# 4.net
KiCad netlist of a schematic drawn in Altium Designer
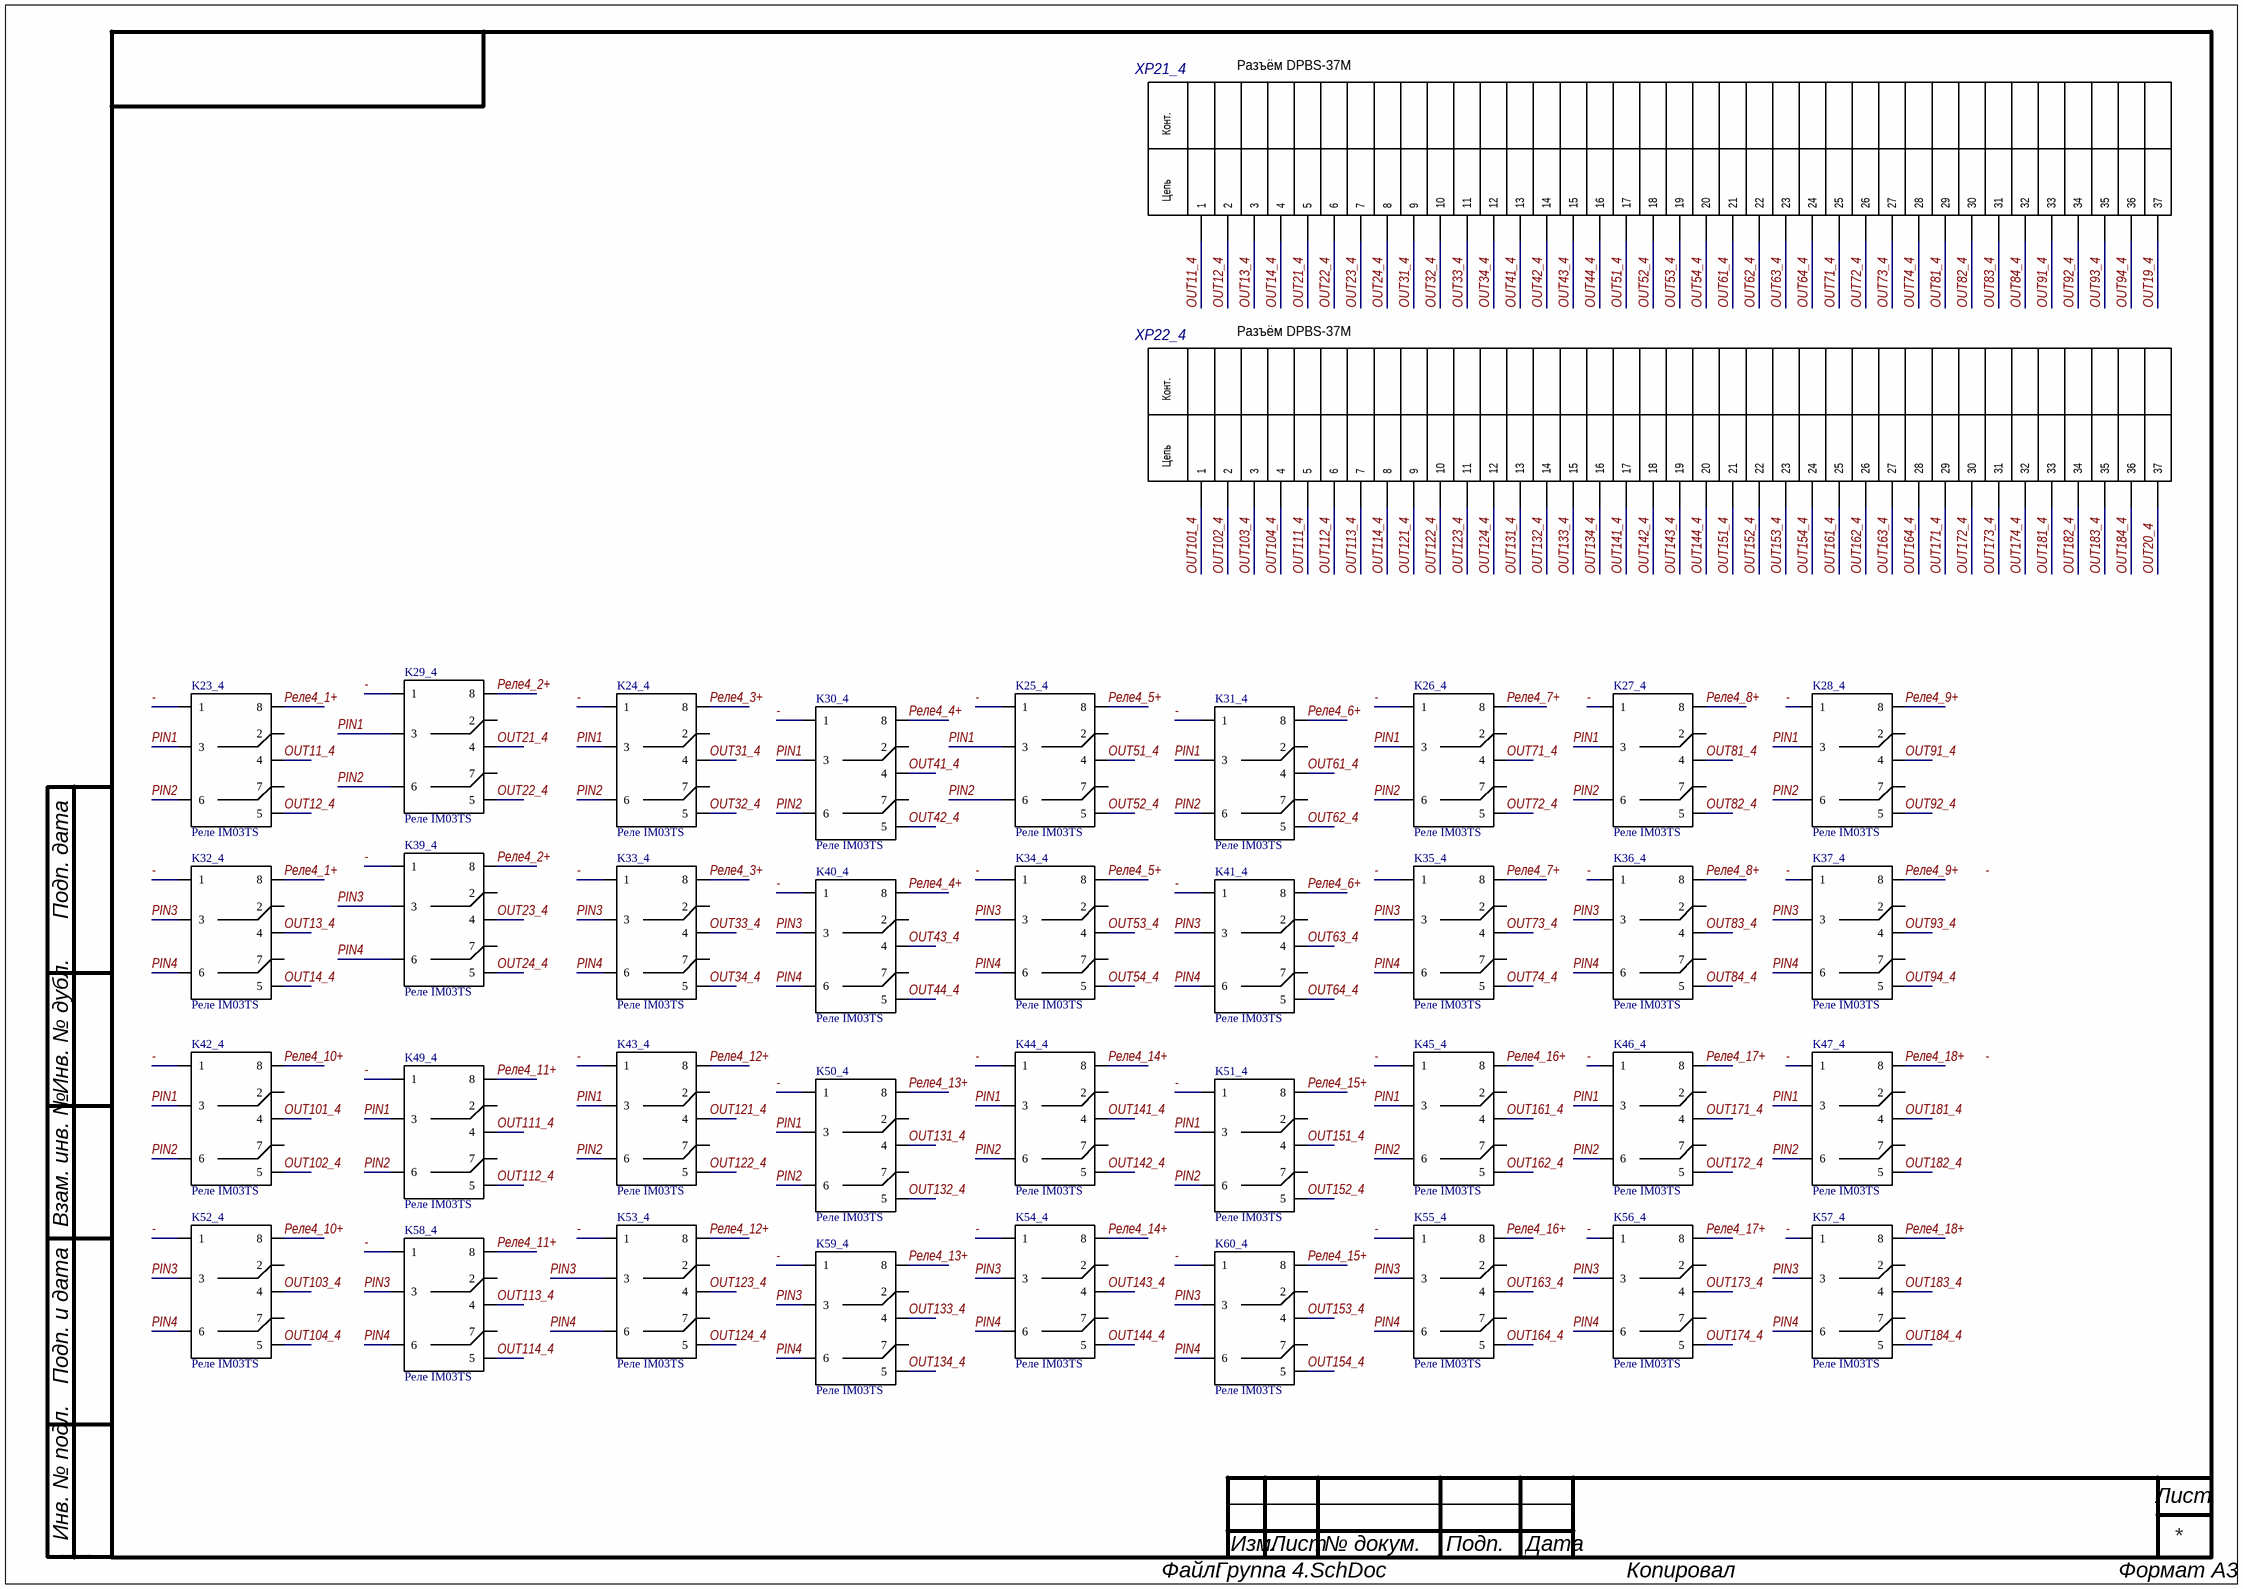
[diagram p0: Группа 4.SchDoc]

(export (version "E")
  (design (tool "Eeschema 10.0.6"))
  (components
    (comp (ref "K23_4")
      (value "Реле IM03TS")
      (footprint "IM03TS")
      (description "Реле")
      (libsource (lib "MainLibrary") (part "IM03TS"))
    )
    (comp (ref "K24_4")
      (value "Реле IM03TS")
      (footprint "IM03TS")
      (description "Реле")
      (libsource (lib "MainLibrary") (part "IM03TS"))
    )
    (comp (ref "K25_4")
      (value "Реле IM03TS")
      (footprint "IM03TS")
      (description "Реле")
      (libsource (lib "MainLibrary") (part "IM03TS"))
    )
    (comp (ref "K26_4")
      (value "Реле IM03TS")
      (footprint "IM03TS")
      (description "Реле")
      (libsource (lib "MainLibrary") (part "IM03TS"))
    )
    (comp (ref "K27_4")
      (value "Реле IM03TS")
      (footprint "IM03TS")
      (description "Реле")
      (libsource (lib "MainLibrary") (part "IM03TS"))
    )
    (comp (ref "K28_4")
      (value "Реле IM03TS")
      (footprint "IM03TS")
      (description "Реле")
      (libsource (lib "MainLibrary") (part "IM03TS"))
    )
    (comp (ref "K29_4")
      (value "Реле IM03TS")
      (footprint "IM03TS")
      (description "Реле")
      (libsource (lib "MainLibrary") (part "IM03TS"))
    )
    (comp (ref "K30_4")
      (value "Реле IM03TS")
      (footprint "IM03TS")
      (description "Реле")
      (libsource (lib "MainLibrary") (part "IM03TS"))
    )
    (comp (ref "K31_4")
      (value "Реле IM03TS")
      (footprint "IM03TS")
      (description "Реле")
      (libsource (lib "MainLibrary") (part "IM03TS"))
    )
    (comp (ref "K32_4")
      (value "Реле IM03TS")
      (footprint "IM03TS")
      (description "Реле")
      (libsource (lib "MainLibrary") (part "IM03TS"))
    )
    (comp (ref "K33_4")
      (value "Реле IM03TS")
      (footprint "IM03TS")
      (description "Реле")
      (libsource (lib "MainLibrary") (part "IM03TS"))
    )
    (comp (ref "K34_4")
      (value "Реле IM03TS")
      (footprint "IM03TS")
      (description "Реле")
      (libsource (lib "MainLibrary") (part "IM03TS"))
    )
    (comp (ref "K35_4")
      (value "Реле IM03TS")
      (footprint "IM03TS")
      (description "Реле")
      (libsource (lib "MainLibrary") (part "IM03TS"))
    )
    (comp (ref "K36_4")
      (value "Реле IM03TS")
      (footprint "IM03TS")
      (description "Реле")
      (libsource (lib "MainLibrary") (part "IM03TS"))
    )
    (comp (ref "K37_4")
      (value "Реле IM03TS")
      (footprint "IM03TS")
      (description "Реле")
      (libsource (lib "MainLibrary") (part "IM03TS"))
    )
    (comp (ref "K39_4")
      (value "Реле IM03TS")
      (footprint "IM03TS")
      (description "Реле")
      (libsource (lib "MainLibrary") (part "IM03TS"))
    )
    (comp (ref "K40_4")
      (value "Реле IM03TS")
      (footprint "IM03TS")
      (description "Реле")
      (libsource (lib "MainLibrary") (part "IM03TS"))
    )
    (comp (ref "K41_4")
      (value "Реле IM03TS")
      (footprint "IM03TS")
      (description "Реле")
      (libsource (lib "MainLibrary") (part "IM03TS"))
    )
    (comp (ref "K42_4")
      (value "Реле IM03TS")
      (footprint "IM03TS")
      (description "Реле")
      (libsource (lib "MainLibrary") (part "IM03TS"))
    )
    (comp (ref "K43_4")
      (value "Реле IM03TS")
      (footprint "IM03TS")
      (description "Реле")
      (libsource (lib "MainLibrary") (part "IM03TS"))
    )
    (comp (ref "K44_4")
      (value "Реле IM03TS")
      (footprint "IM03TS")
      (description "Реле")
      (libsource (lib "MainLibrary") (part "IM03TS"))
    )
    (comp (ref "K45_4")
      (value "Реле IM03TS")
      (footprint "IM03TS")
      (description "Реле")
      (libsource (lib "MainLibrary") (part "IM03TS"))
    )
    (comp (ref "K46_4")
      (value "Реле IM03TS")
      (footprint "IM03TS")
      (description "Реле")
      (libsource (lib "MainLibrary") (part "IM03TS"))
    )
    (comp (ref "K47_4")
      (value "Реле IM03TS")
      (footprint "IM03TS")
      (description "Реле")
      (libsource (lib "MainLibrary") (part "IM03TS"))
    )
    (comp (ref "K49_4")
      (value "Реле IM03TS")
      (footprint "IM03TS")
      (description "Реле")
      (libsource (lib "MainLibrary") (part "IM03TS"))
    )
    (comp (ref "K50_4")
      (value "Реле IM03TS")
      (footprint "IM03TS")
      (description "Реле")
      (libsource (lib "MainLibrary") (part "IM03TS"))
    )
    (comp (ref "K51_4")
      (value "Реле IM03TS")
      (footprint "IM03TS")
      (description "Реле")
      (libsource (lib "MainLibrary") (part "IM03TS"))
    )
    (comp (ref "K52_4")
      (value "Реле IM03TS")
      (footprint "IM03TS")
      (description "Реле")
      (libsource (lib "MainLibrary") (part "IM03TS"))
    )
    (comp (ref "K53_4")
      (value "Реле IM03TS")
      (footprint "IM03TS")
      (description "Реле")
      (libsource (lib "MainLibrary") (part "IM03TS"))
    )
    (comp (ref "K54_4")
      (value "Реле IM03TS")
      (footprint "IM03TS")
      (description "Реле")
      (libsource (lib "MainLibrary") (part "IM03TS"))
    )
    (comp (ref "K55_4")
      (value "Реле IM03TS")
      (footprint "IM03TS")
      (description "Реле")
      (libsource (lib "MainLibrary") (part "IM03TS"))
    )
    (comp (ref "K56_4")
      (value "Реле IM03TS")
      (footprint "IM03TS")
      (description "Реле")
      (libsource (lib "MainLibrary") (part "IM03TS"))
    )
    (comp (ref "K57_4")
      (value "Реле IM03TS")
      (footprint "IM03TS")
      (description "Реле")
      (libsource (lib "MainLibrary") (part "IM03TS"))
    )
    (comp (ref "K58_4")
      (value "Реле IM03TS")
      (footprint "IM03TS")
      (description "Реле")
      (libsource (lib "MainLibrary") (part "IM03TS"))
    )
    (comp (ref "K59_4")
      (value "Реле IM03TS")
      (footprint "IM03TS")
      (description "Реле")
      (libsource (lib "MainLibrary") (part "IM03TS"))
    )
    (comp (ref "K60_4")
      (value "Реле IM03TS")
      (footprint "IM03TS")
      (description "Реле")
      (libsource (lib "MainLibrary") (part "IM03TS"))
    )
    (comp (ref "XP21_4")
      (value "Разъём DPBS-37M")
      (footprint "DPBS-37M")
      (libsource (lib "MainLibrary") (part "DPBS-37M"))
    )
    (comp (ref "XP22_4")
      (value "Разъём DPBS-37M")
      (footprint "DPBS-37M")
      (libsource (lib "MainLibrary") (part "DPBS-37M"))
    )
  )
  (nets
    (net (code "1") (name "/-") (class "Default")
      (node (ref "K23_4") (pin "1") (pinfunction "1_1") (pintype "passive"))
      (node (ref "K24_4") (pin "1") (pinfunction "1_1") (pintype "passive"))
      (node (ref "K25_4") (pin "1") (pinfunction "1_1") (pintype "passive"))
      (node (ref "K26_4") (pin "1") (pinfunction "1_1") (pintype "passive"))
      (node (ref "K27_4") (pin "1") (pinfunction "1_1") (pintype "passive"))
      (node (ref "K28_4") (pin "1") (pinfunction "1_1") (pintype "passive"))
      (node (ref "K29_4") (pin "1") (pinfunction "1_1") (pintype "passive"))
      (node (ref "K30_4") (pin "1") (pinfunction "1_1") (pintype "passive"))
      (node (ref "K31_4") (pin "1") (pinfunction "1_1") (pintype "passive"))
      (node (ref "K32_4") (pin "1") (pinfunction "1_1") (pintype "passive"))
      (node (ref "K33_4") (pin "1") (pinfunction "1_1") (pintype "passive"))
      (node (ref "K34_4") (pin "1") (pinfunction "1_1") (pintype "passive"))
      (node (ref "K35_4") (pin "1") (pinfunction "1_1") (pintype "passive"))
      (node (ref "K36_4") (pin "1") (pinfunction "1_1") (pintype "passive"))
      (node (ref "K37_4") (pin "1") (pinfunction "1_1") (pintype "passive"))
      (node (ref "K39_4") (pin "1") (pinfunction "1_1") (pintype "passive"))
      (node (ref "K40_4") (pin "1") (pinfunction "1_1") (pintype "passive"))
      (node (ref "K41_4") (pin "1") (pinfunction "1_1") (pintype "passive"))
      (node (ref "K42_4") (pin "1") (pinfunction "1_1") (pintype "passive"))
      (node (ref "K43_4") (pin "1") (pinfunction "1_1") (pintype "passive"))
      (node (ref "K44_4") (pin "1") (pinfunction "1_1") (pintype "passive"))
      (node (ref "K45_4") (pin "1") (pinfunction "1_1") (pintype "passive"))
      (node (ref "K46_4") (pin "1") (pinfunction "1_1") (pintype "passive"))
      (node (ref "K47_4") (pin "1") (pinfunction "1_1") (pintype "passive"))
      (node (ref "K49_4") (pin "1") (pinfunction "1_1") (pintype "passive"))
      (node (ref "K50_4") (pin "1") (pinfunction "1_1") (pintype "passive"))
      (node (ref "K51_4") (pin "1") (pinfunction "1_1") (pintype "passive"))
      (node (ref "K52_4") (pin "1") (pinfunction "1_1") (pintype "passive"))
      (node (ref "K53_4") (pin "1") (pinfunction "1_1") (pintype "passive"))
      (node (ref "K54_4") (pin "1") (pinfunction "1_1") (pintype "passive"))
      (node (ref "K55_4") (pin "1") (pinfunction "1_1") (pintype "passive"))
      (node (ref "K56_4") (pin "1") (pinfunction "1_1") (pintype "passive"))
      (node (ref "K57_4") (pin "1") (pinfunction "1_1") (pintype "passive"))
      (node (ref "K58_4") (pin "1") (pinfunction "1_1") (pintype "passive"))
      (node (ref "K59_4") (pin "1") (pinfunction "1_1") (pintype "passive"))
      (node (ref "K60_4") (pin "1") (pinfunction "1_1") (pintype "passive"))
    )
    (net (code "2") (name "/OUT11_4") (class "Default")
      (node (ref "K23_4") (pin "4") (pinfunction "4_4") (pintype "passive"))
      (node (ref "XP21_4") (pin "1") (pinfunction "1_1") (pintype "passive"))
    )
    (net (code "3") (name "/OUT12_4") (class "Default")
      (node (ref "K23_4") (pin "5") (pinfunction "5_5") (pintype "passive"))
      (node (ref "XP21_4") (pin "2") (pinfunction "2_2") (pintype "passive"))
    )
    (net (code "4") (name "/OUT13_4") (class "Default")
      (node (ref "K32_4") (pin "4") (pinfunction "4_4") (pintype "passive"))
      (node (ref "XP21_4") (pin "3") (pinfunction "3_3") (pintype "passive"))
    )
    (net (code "5") (name "/OUT14_4") (class "Default")
      (node (ref "K32_4") (pin "5") (pinfunction "5_5") (pintype "passive"))
      (node (ref "XP21_4") (pin "4") (pinfunction "4_4") (pintype "passive"))
    )
    (net (code "6") (name "/OUT19_4") (class "Default")
      (node (ref "XP21_4") (pin "37") (pinfunction "37_37") (pintype "passive"))
    )
    (net (code "7") (name "/OUT20_4") (class "Default")
      (node (ref "XP22_4") (pin "37") (pinfunction "37_37") (pintype "passive"))
    )
    (net (code "8") (name "/OUT21_4") (class "Default")
      (node (ref "K29_4") (pin "4") (pinfunction "4_4") (pintype "passive"))
      (node (ref "XP21_4") (pin "5") (pinfunction "5_5") (pintype "passive"))
    )
    (net (code "9") (name "/OUT22_4") (class "Default")
      (node (ref "K29_4") (pin "5") (pinfunction "5_5") (pintype "passive"))
      (node (ref "XP21_4") (pin "6") (pinfunction "6_6") (pintype "passive"))
    )
    (net (code "10") (name "/OUT23_4") (class "Default")
      (node (ref "K39_4") (pin "4") (pinfunction "4_4") (pintype "passive"))
      (node (ref "XP21_4") (pin "7") (pinfunction "7_7") (pintype "passive"))
    )
    (net (code "11") (name "/OUT24_4") (class "Default")
      (node (ref "K39_4") (pin "5") (pinfunction "5_5") (pintype "passive"))
      (node (ref "XP21_4") (pin "8") (pinfunction "8_8") (pintype "passive"))
    )
    (net (code "12") (name "/OUT31_4") (class "Default")
      (node (ref "K24_4") (pin "4") (pinfunction "4_4") (pintype "passive"))
      (node (ref "XP21_4") (pin "9") (pinfunction "9_9") (pintype "passive"))
    )
    (net (code "13") (name "/OUT32_4") (class "Default")
      (node (ref "K24_4") (pin "5") (pinfunction "5_5") (pintype "passive"))
      (node (ref "XP21_4") (pin "10") (pinfunction "10_10") (pintype "passive"))
    )
    (net (code "14") (name "/OUT33_4") (class "Default")
      (node (ref "K33_4") (pin "4") (pinfunction "4_4") (pintype "passive"))
      (node (ref "XP21_4") (pin "11") (pinfunction "11_11") (pintype "passive"))
    )
    (net (code "15") (name "/OUT34_4") (class "Default")
      (node (ref "K33_4") (pin "5") (pinfunction "5_5") (pintype "passive"))
      (node (ref "XP21_4") (pin "12") (pinfunction "12_12") (pintype "passive"))
    )
    (net (code "16") (name "/OUT41_4") (class "Default")
      (node (ref "K30_4") (pin "4") (pinfunction "4_4") (pintype "passive"))
      (node (ref "XP21_4") (pin "13") (pinfunction "13_13") (pintype "passive"))
    )
    (net (code "17") (name "/OUT42_4") (class "Default")
      (node (ref "K30_4") (pin "5") (pinfunction "5_5") (pintype "passive"))
      (node (ref "XP21_4") (pin "14") (pinfunction "14_14") (pintype "passive"))
    )
    (net (code "18") (name "/OUT43_4") (class "Default")
      (node (ref "K40_4") (pin "4") (pinfunction "4_4") (pintype "passive"))
      (node (ref "XP21_4") (pin "15") (pinfunction "15_15") (pintype "passive"))
    )
    (net (code "19") (name "/OUT44_4") (class "Default")
      (node (ref "K40_4") (pin "5") (pinfunction "5_5") (pintype "passive"))
      (node (ref "XP21_4") (pin "16") (pinfunction "16_16") (pintype "passive"))
    )
    (net (code "20") (name "/OUT51_4") (class "Default")
      (node (ref "K25_4") (pin "4") (pinfunction "4_4") (pintype "passive"))
      (node (ref "XP21_4") (pin "17") (pinfunction "17_17") (pintype "passive"))
    )
    (net (code "21") (name "/OUT52_4") (class "Default")
      (node (ref "K25_4") (pin "5") (pinfunction "5_5") (pintype "passive"))
      (node (ref "XP21_4") (pin "18") (pinfunction "18_18") (pintype "passive"))
    )
    (net (code "22") (name "/OUT53_4") (class "Default")
      (node (ref "K34_4") (pin "4") (pinfunction "4_4") (pintype "passive"))
      (node (ref "XP21_4") (pin "19") (pinfunction "19_19") (pintype "passive"))
    )
    (net (code "23") (name "/OUT54_4") (class "Default")
      (node (ref "K34_4") (pin "5") (pinfunction "5_5") (pintype "passive"))
      (node (ref "XP21_4") (pin "20") (pinfunction "20_20") (pintype "passive"))
    )
    (net (code "24") (name "/OUT61_4") (class "Default")
      (node (ref "K31_4") (pin "4") (pinfunction "4_4") (pintype "passive"))
      (node (ref "XP21_4") (pin "21") (pinfunction "21_21") (pintype "passive"))
    )
    (net (code "25") (name "/OUT62_4") (class "Default")
      (node (ref "K31_4") (pin "5") (pinfunction "5_5") (pintype "passive"))
      (node (ref "XP21_4") (pin "22") (pinfunction "22_22") (pintype "passive"))
    )
    (net (code "26") (name "/OUT63_4") (class "Default")
      (node (ref "K41_4") (pin "4") (pinfunction "4_4") (pintype "passive"))
      (node (ref "XP21_4") (pin "23") (pinfunction "23_23") (pintype "passive"))
    )
    (net (code "27") (name "/OUT64_4") (class "Default")
      (node (ref "K41_4") (pin "5") (pinfunction "5_5") (pintype "passive"))
      (node (ref "XP21_4") (pin "24") (pinfunction "24_24") (pintype "passive"))
    )
    (net (code "28") (name "/OUT71_4") (class "Default")
      (node (ref "K26_4") (pin "4") (pinfunction "4_4") (pintype "passive"))
      (node (ref "XP21_4") (pin "25") (pinfunction "25_25") (pintype "passive"))
    )
    (net (code "29") (name "/OUT72_4") (class "Default")
      (node (ref "K26_4") (pin "5") (pinfunction "5_5") (pintype "passive"))
      (node (ref "XP21_4") (pin "26") (pinfunction "26_26") (pintype "passive"))
    )
    (net (code "30") (name "/OUT73_4") (class "Default")
      (node (ref "K35_4") (pin "4") (pinfunction "4_4") (pintype "passive"))
      (node (ref "XP21_4") (pin "27") (pinfunction "27_27") (pintype "passive"))
    )
    (net (code "31") (name "/OUT74_4") (class "Default")
      (node (ref "K35_4") (pin "5") (pinfunction "5_5") (pintype "passive"))
      (node (ref "XP21_4") (pin "28") (pinfunction "28_28") (pintype "passive"))
    )
    (net (code "32") (name "/OUT81_4") (class "Default")
      (node (ref "K27_4") (pin "4") (pinfunction "4_4") (pintype "passive"))
      (node (ref "XP21_4") (pin "29") (pinfunction "29_29") (pintype "passive"))
    )
    (net (code "33") (name "/OUT82_4") (class "Default")
      (node (ref "K27_4") (pin "5") (pinfunction "5_5") (pintype "passive"))
      (node (ref "XP21_4") (pin "30") (pinfunction "30_30") (pintype "passive"))
    )
    (net (code "34") (name "/OUT83_4") (class "Default")
      (node (ref "K36_4") (pin "4") (pinfunction "4_4") (pintype "passive"))
      (node (ref "XP21_4") (pin "31") (pinfunction "31_31") (pintype "passive"))
    )
    (net (code "35") (name "/OUT84_4") (class "Default")
      (node (ref "K36_4") (pin "5") (pinfunction "5_5") (pintype "passive"))
      (node (ref "XP21_4") (pin "32") (pinfunction "32_32") (pintype "passive"))
    )
    (net (code "36") (name "/OUT91_4") (class "Default")
      (node (ref "K28_4") (pin "4") (pinfunction "4_4") (pintype "passive"))
      (node (ref "XP21_4") (pin "33") (pinfunction "33_33") (pintype "passive"))
    )
    (net (code "37") (name "/OUT92_4") (class "Default")
      (node (ref "K28_4") (pin "5") (pinfunction "5_5") (pintype "passive"))
      (node (ref "XP21_4") (pin "34") (pinfunction "34_34") (pintype "passive"))
    )
    (net (code "38") (name "/OUT93_4") (class "Default")
      (node (ref "K37_4") (pin "4") (pinfunction "4_4") (pintype "passive"))
      (node (ref "XP21_4") (pin "35") (pinfunction "35_35") (pintype "passive"))
    )
    (net (code "39") (name "/OUT94_4") (class "Default")
      (node (ref "K37_4") (pin "5") (pinfunction "5_5") (pintype "passive"))
      (node (ref "XP21_4") (pin "36") (pinfunction "36_36") (pintype "passive"))
    )
    (net (code "40") (name "/OUT101_4") (class "Default")
      (node (ref "K42_4") (pin "4") (pinfunction "4_4") (pintype "passive"))
      (node (ref "XP22_4") (pin "1") (pinfunction "1_1") (pintype "passive"))
    )
    (net (code "41") (name "/OUT102_4") (class "Default")
      (node (ref "K42_4") (pin "5") (pinfunction "5_5") (pintype "passive"))
      (node (ref "XP22_4") (pin "2") (pinfunction "2_2") (pintype "passive"))
    )
    (net (code "42") (name "/OUT103_4") (class "Default")
      (node (ref "K52_4") (pin "4") (pinfunction "4_4") (pintype "passive"))
      (node (ref "XP22_4") (pin "3") (pinfunction "3_3") (pintype "passive"))
    )
    (net (code "43") (name "/OUT104_4") (class "Default")
      (node (ref "K52_4") (pin "5") (pinfunction "5_5") (pintype "passive"))
      (node (ref "XP22_4") (pin "4") (pinfunction "4_4") (pintype "passive"))
    )
    (net (code "44") (name "/OUT111_4") (class "Default")
      (node (ref "K49_4") (pin "4") (pinfunction "4_4") (pintype "passive"))
      (node (ref "XP22_4") (pin "5") (pinfunction "5_5") (pintype "passive"))
    )
    (net (code "45") (name "/OUT112_4") (class "Default")
      (node (ref "K49_4") (pin "5") (pinfunction "5_5") (pintype "passive"))
      (node (ref "XP22_4") (pin "6") (pinfunction "6_6") (pintype "passive"))
    )
    (net (code "46") (name "/OUT113_4") (class "Default")
      (node (ref "K58_4") (pin "4") (pinfunction "4_4") (pintype "passive"))
      (node (ref "XP22_4") (pin "7") (pinfunction "7_7") (pintype "passive"))
    )
    (net (code "47") (name "/OUT114_4") (class "Default")
      (node (ref "K58_4") (pin "5") (pinfunction "5_5") (pintype "passive"))
      (node (ref "XP22_4") (pin "8") (pinfunction "8_8") (pintype "passive"))
    )
    (net (code "48") (name "/OUT121_4") (class "Default")
      (node (ref "K43_4") (pin "4") (pinfunction "4_4") (pintype "passive"))
      (node (ref "XP22_4") (pin "9") (pinfunction "9_9") (pintype "passive"))
    )
    (net (code "49") (name "/OUT122_4") (class "Default")
      (node (ref "K43_4") (pin "5") (pinfunction "5_5") (pintype "passive"))
      (node (ref "XP22_4") (pin "10") (pinfunction "10_10") (pintype "passive"))
    )
    (net (code "50") (name "/OUT123_4") (class "Default")
      (node (ref "K53_4") (pin "4") (pinfunction "4_4") (pintype "passive"))
      (node (ref "XP22_4") (pin "11") (pinfunction "11_11") (pintype "passive"))
    )
    (net (code "51") (name "/OUT124_4") (class "Default")
      (node (ref "K53_4") (pin "5") (pinfunction "5_5") (pintype "passive"))
      (node (ref "XP22_4") (pin "12") (pinfunction "12_12") (pintype "passive"))
    )
    (net (code "52") (name "/OUT131_4") (class "Default")
      (node (ref "K50_4") (pin "4") (pinfunction "4_4") (pintype "passive"))
      (node (ref "XP22_4") (pin "13") (pinfunction "13_13") (pintype "passive"))
    )
    (net (code "53") (name "/OUT132_4") (class "Default")
      (node (ref "K50_4") (pin "5") (pinfunction "5_5") (pintype "passive"))
      (node (ref "XP22_4") (pin "14") (pinfunction "14_14") (pintype "passive"))
    )
    (net (code "54") (name "/OUT133_4") (class "Default")
      (node (ref "K59_4") (pin "4") (pinfunction "4_4") (pintype "passive"))
      (node (ref "XP22_4") (pin "15") (pinfunction "15_15") (pintype "passive"))
    )
    (net (code "55") (name "/OUT134_4") (class "Default")
      (node (ref "K59_4") (pin "5") (pinfunction "5_5") (pintype "passive"))
      (node (ref "XP22_4") (pin "16") (pinfunction "16_16") (pintype "passive"))
    )
    (net (code "56") (name "/OUT141_4") (class "Default")
      (node (ref "K44_4") (pin "4") (pinfunction "4_4") (pintype "passive"))
      (node (ref "XP22_4") (pin "17") (pinfunction "17_17") (pintype "passive"))
    )
    (net (code "57") (name "/OUT142_4") (class "Default")
      (node (ref "K44_4") (pin "5") (pinfunction "5_5") (pintype "passive"))
      (node (ref "XP22_4") (pin "18") (pinfunction "18_18") (pintype "passive"))
    )
    (net (code "58") (name "/OUT143_4") (class "Default")
      (node (ref "K54_4") (pin "4") (pinfunction "4_4") (pintype "passive"))
      (node (ref "XP22_4") (pin "19") (pinfunction "19_19") (pintype "passive"))
    )
    (net (code "59") (name "/OUT144_4") (class "Default")
      (node (ref "K54_4") (pin "5") (pinfunction "5_5") (pintype "passive"))
      (node (ref "XP22_4") (pin "20") (pinfunction "20_20") (pintype "passive"))
    )
    (net (code "60") (name "/OUT151_4") (class "Default")
      (node (ref "K51_4") (pin "4") (pinfunction "4_4") (pintype "passive"))
      (node (ref "XP22_4") (pin "21") (pinfunction "21_21") (pintype "passive"))
    )
    (net (code "61") (name "/OUT152_4") (class "Default")
      (node (ref "K51_4") (pin "5") (pinfunction "5_5") (pintype "passive"))
      (node (ref "XP22_4") (pin "22") (pinfunction "22_22") (pintype "passive"))
    )
    (net (code "62") (name "/OUT153_4") (class "Default")
      (node (ref "K60_4") (pin "4") (pinfunction "4_4") (pintype "passive"))
      (node (ref "XP22_4") (pin "23") (pinfunction "23_23") (pintype "passive"))
    )
    (net (code "63") (name "/OUT154_4") (class "Default")
      (node (ref "K60_4") (pin "5") (pinfunction "5_5") (pintype "passive"))
      (node (ref "XP22_4") (pin "24") (pinfunction "24_24") (pintype "passive"))
    )
    (net (code "64") (name "/OUT161_4") (class "Default")
      (node (ref "K45_4") (pin "4") (pinfunction "4_4") (pintype "passive"))
      (node (ref "XP22_4") (pin "25") (pinfunction "25_25") (pintype "passive"))
    )
    (net (code "65") (name "/OUT162_4") (class "Default")
      (node (ref "K45_4") (pin "5") (pinfunction "5_5") (pintype "passive"))
      (node (ref "XP22_4") (pin "26") (pinfunction "26_26") (pintype "passive"))
    )
    (net (code "66") (name "/OUT163_4") (class "Default")
      (node (ref "K55_4") (pin "4") (pinfunction "4_4") (pintype "passive"))
      (node (ref "XP22_4") (pin "27") (pinfunction "27_27") (pintype "passive"))
    )
    (net (code "67") (name "/OUT164_4") (class "Default")
      (node (ref "K55_4") (pin "5") (pinfunction "5_5") (pintype "passive"))
      (node (ref "XP22_4") (pin "28") (pinfunction "28_28") (pintype "passive"))
    )
    (net (code "68") (name "/OUT171_4") (class "Default")
      (node (ref "K46_4") (pin "4") (pinfunction "4_4") (pintype "passive"))
      (node (ref "XP22_4") (pin "29") (pinfunction "29_29") (pintype "passive"))
    )
    (net (code "69") (name "/OUT172_4") (class "Default")
      (node (ref "K46_4") (pin "5") (pinfunction "5_5") (pintype "passive"))
      (node (ref "XP22_4") (pin "30") (pinfunction "30_30") (pintype "passive"))
    )
    (net (code "70") (name "/OUT173_4") (class "Default")
      (node (ref "K56_4") (pin "4") (pinfunction "4_4") (pintype "passive"))
      (node (ref "XP22_4") (pin "31") (pinfunction "31_31") (pintype "passive"))
    )
    (net (code "71") (name "/OUT174_4") (class "Default")
      (node (ref "K56_4") (pin "5") (pinfunction "5_5") (pintype "passive"))
      (node (ref "XP22_4") (pin "32") (pinfunction "32_32") (pintype "passive"))
    )
    (net (code "72") (name "/OUT181_4") (class "Default")
      (node (ref "K47_4") (pin "4") (pinfunction "4_4") (pintype "passive"))
      (node (ref "XP22_4") (pin "33") (pinfunction "33_33") (pintype "passive"))
    )
    (net (code "73") (name "/OUT182_4") (class "Default")
      (node (ref "K47_4") (pin "5") (pinfunction "5_5") (pintype "passive"))
      (node (ref "XP22_4") (pin "34") (pinfunction "34_34") (pintype "passive"))
    )
    (net (code "74") (name "/OUT183_4") (class "Default")
      (node (ref "K57_4") (pin "4") (pinfunction "4_4") (pintype "passive"))
      (node (ref "XP22_4") (pin "35") (pinfunction "35_35") (pintype "passive"))
    )
    (net (code "75") (name "/OUT184_4") (class "Default")
      (node (ref "K57_4") (pin "5") (pinfunction "5_5") (pintype "passive"))
      (node (ref "XP22_4") (pin "36") (pinfunction "36_36") (pintype "passive"))
    )
    (net (code "76") (name "/PIN1") (class "Default")
      (node (ref "K23_4") (pin "3") (pinfunction "3_3") (pintype "passive"))
      (node (ref "K24_4") (pin "3") (pinfunction "3_3") (pintype "passive"))
      (node (ref "K25_4") (pin "3") (pinfunction "3_3") (pintype "passive"))
      (node (ref "K26_4") (pin "3") (pinfunction "3_3") (pintype "passive"))
      (node (ref "K27_4") (pin "3") (pinfunction "3_3") (pintype "passive"))
      (node (ref "K28_4") (pin "3") (pinfunction "3_3") (pintype "passive"))
      (node (ref "K29_4") (pin "3") (pinfunction "3_3") (pintype "passive"))
      (node (ref "K30_4") (pin "3") (pinfunction "3_3") (pintype "passive"))
      (node (ref "K31_4") (pin "3") (pinfunction "3_3") (pintype "passive"))
      (node (ref "K42_4") (pin "3") (pinfunction "3_3") (pintype "passive"))
      (node (ref "K43_4") (pin "3") (pinfunction "3_3") (pintype "passive"))
      (node (ref "K44_4") (pin "3") (pinfunction "3_3") (pintype "passive"))
      (node (ref "K45_4") (pin "3") (pinfunction "3_3") (pintype "passive"))
      (node (ref "K46_4") (pin "3") (pinfunction "3_3") (pintype "passive"))
      (node (ref "K47_4") (pin "3") (pinfunction "3_3") (pintype "passive"))
      (node (ref "K49_4") (pin "3") (pinfunction "3_3") (pintype "passive"))
      (node (ref "K50_4") (pin "3") (pinfunction "3_3") (pintype "passive"))
      (node (ref "K51_4") (pin "3") (pinfunction "3_3") (pintype "passive"))
    )
    (net (code "77") (name "/PIN2") (class "Default")
      (node (ref "K23_4") (pin "6") (pinfunction "6_6") (pintype "passive"))
      (node (ref "K24_4") (pin "6") (pinfunction "6_6") (pintype "passive"))
      (node (ref "K25_4") (pin "6") (pinfunction "6_6") (pintype "passive"))
      (node (ref "K26_4") (pin "6") (pinfunction "6_6") (pintype "passive"))
      (node (ref "K27_4") (pin "6") (pinfunction "6_6") (pintype "passive"))
      (node (ref "K28_4") (pin "6") (pinfunction "6_6") (pintype "passive"))
      (node (ref "K29_4") (pin "6") (pinfunction "6_6") (pintype "passive"))
      (node (ref "K30_4") (pin "6") (pinfunction "6_6") (pintype "passive"))
      (node (ref "K31_4") (pin "6") (pinfunction "6_6") (pintype "passive"))
      (node (ref "K42_4") (pin "6") (pinfunction "6_6") (pintype "passive"))
      (node (ref "K43_4") (pin "6") (pinfunction "6_6") (pintype "passive"))
      (node (ref "K44_4") (pin "6") (pinfunction "6_6") (pintype "passive"))
      (node (ref "K45_4") (pin "6") (pinfunction "6_6") (pintype "passive"))
      (node (ref "K46_4") (pin "6") (pinfunction "6_6") (pintype "passive"))
      (node (ref "K47_4") (pin "6") (pinfunction "6_6") (pintype "passive"))
      (node (ref "K49_4") (pin "6") (pinfunction "6_6") (pintype "passive"))
      (node (ref "K50_4") (pin "6") (pinfunction "6_6") (pintype "passive"))
      (node (ref "K51_4") (pin "6") (pinfunction "6_6") (pintype "passive"))
    )
    (net (code "78") (name "/PIN3") (class "Default")
      (node (ref "K32_4") (pin "3") (pinfunction "3_3") (pintype "passive"))
      (node (ref "K33_4") (pin "3") (pinfunction "3_3") (pintype "passive"))
      (node (ref "K34_4") (pin "3") (pinfunction "3_3") (pintype "passive"))
      (node (ref "K35_4") (pin "3") (pinfunction "3_3") (pintype "passive"))
      (node (ref "K36_4") (pin "3") (pinfunction "3_3") (pintype "passive"))
      (node (ref "K37_4") (pin "3") (pinfunction "3_3") (pintype "passive"))
      (node (ref "K39_4") (pin "3") (pinfunction "3_3") (pintype "passive"))
      (node (ref "K40_4") (pin "3") (pinfunction "3_3") (pintype "passive"))
      (node (ref "K41_4") (pin "3") (pinfunction "3_3") (pintype "passive"))
      (node (ref "K52_4") (pin "3") (pinfunction "3_3") (pintype "passive"))
      (node (ref "K53_4") (pin "3") (pinfunction "3_3") (pintype "passive"))
      (node (ref "K54_4") (pin "3") (pinfunction "3_3") (pintype "passive"))
      (node (ref "K55_4") (pin "3") (pinfunction "3_3") (pintype "passive"))
      (node (ref "K56_4") (pin "3") (pinfunction "3_3") (pintype "passive"))
      (node (ref "K57_4") (pin "3") (pinfunction "3_3") (pintype "passive"))
      (node (ref "K58_4") (pin "3") (pinfunction "3_3") (pintype "passive"))
      (node (ref "K59_4") (pin "3") (pinfunction "3_3") (pintype "passive"))
      (node (ref "K60_4") (pin "3") (pinfunction "3_3") (pintype "passive"))
    )
    (net (code "79") (name "/PIN4") (class "Default")
      (node (ref "K32_4") (pin "6") (pinfunction "6_6") (pintype "passive"))
      (node (ref "K33_4") (pin "6") (pinfunction "6_6") (pintype "passive"))
      (node (ref "K34_4") (pin "6") (pinfunction "6_6") (pintype "passive"))
      (node (ref "K35_4") (pin "6") (pinfunction "6_6") (pintype "passive"))
      (node (ref "K36_4") (pin "6") (pinfunction "6_6") (pintype "passive"))
      (node (ref "K37_4") (pin "6") (pinfunction "6_6") (pintype "passive"))
      (node (ref "K39_4") (pin "6") (pinfunction "6_6") (pintype "passive"))
      (node (ref "K40_4") (pin "6") (pinfunction "6_6") (pintype "passive"))
      (node (ref "K41_4") (pin "6") (pinfunction "6_6") (pintype "passive"))
      (node (ref "K52_4") (pin "6") (pinfunction "6_6") (pintype "passive"))
      (node (ref "K53_4") (pin "6") (pinfunction "6_6") (pintype "passive"))
      (node (ref "K54_4") (pin "6") (pinfunction "6_6") (pintype "passive"))
      (node (ref "K55_4") (pin "6") (pinfunction "6_6") (pintype "passive"))
      (node (ref "K56_4") (pin "6") (pinfunction "6_6") (pintype "passive"))
      (node (ref "K57_4") (pin "6") (pinfunction "6_6") (pintype "passive"))
      (node (ref "K58_4") (pin "6") (pinfunction "6_6") (pintype "passive"))
      (node (ref "K59_4") (pin "6") (pinfunction "6_6") (pintype "passive"))
      (node (ref "K60_4") (pin "6") (pinfunction "6_6") (pintype "passive"))
    )
    (net (code "80") (name "/Реле4_1+") (class "Default")
      (node (ref "K23_4") (pin "8") (pinfunction "8_8") (pintype "passive"))
      (node (ref "K32_4") (pin "8") (pinfunction "8_8") (pintype "passive"))
    )
    (net (code "81") (name "/Реле4_2+") (class "Default")
      (node (ref "K29_4") (pin "8") (pinfunction "8_8") (pintype "passive"))
      (node (ref "K39_4") (pin "8") (pinfunction "8_8") (pintype "passive"))
    )
    (net (code "82") (name "/Реле4_3+") (class "Default")
      (node (ref "K24_4") (pin "8") (pinfunction "8_8") (pintype "passive"))
      (node (ref "K33_4") (pin "8") (pinfunction "8_8") (pintype "passive"))
    )
    (net (code "83") (name "/Реле4_4+") (class "Default")
      (node (ref "K30_4") (pin "8") (pinfunction "8_8") (pintype "passive"))
      (node (ref "K40_4") (pin "8") (pinfunction "8_8") (pintype "passive"))
    )
    (net (code "84") (name "/Реле4_5+") (class "Default")
      (node (ref "K25_4") (pin "8") (pinfunction "8_8") (pintype "passive"))
      (node (ref "K34_4") (pin "8") (pinfunction "8_8") (pintype "passive"))
    )
    (net (code "85") (name "/Реле4_6+") (class "Default")
      (node (ref "K31_4") (pin "8") (pinfunction "8_8") (pintype "passive"))
      (node (ref "K41_4") (pin "8") (pinfunction "8_8") (pintype "passive"))
    )
    (net (code "86") (name "/Реле4_7+") (class "Default")
      (node (ref "K26_4") (pin "8") (pinfunction "8_8") (pintype "passive"))
      (node (ref "K35_4") (pin "8") (pinfunction "8_8") (pintype "passive"))
    )
    (net (code "87") (name "/Реле4_8+") (class "Default")
      (node (ref "K27_4") (pin "8") (pinfunction "8_8") (pintype "passive"))
      (node (ref "K36_4") (pin "8") (pinfunction "8_8") (pintype "passive"))
    )
    (net (code "88") (name "/Реле4_9+") (class "Default")
      (node (ref "K28_4") (pin "8") (pinfunction "8_8") (pintype "passive"))
      (node (ref "K37_4") (pin "8") (pinfunction "8_8") (pintype "passive"))
    )
    (net (code "89") (name "/Реле4_10+") (class "Default")
      (node (ref "K42_4") (pin "8") (pinfunction "8_8") (pintype "passive"))
      (node (ref "K52_4") (pin "8") (pinfunction "8_8") (pintype "passive"))
    )
    (net (code "90") (name "/Реле4_11+") (class "Default")
      (node (ref "K49_4") (pin "8") (pinfunction "8_8") (pintype "passive"))
      (node (ref "K58_4") (pin "8") (pinfunction "8_8") (pintype "passive"))
    )
    (net (code "91") (name "/Реле4_12+") (class "Default")
      (node (ref "K43_4") (pin "8") (pinfunction "8_8") (pintype "passive"))
      (node (ref "K53_4") (pin "8") (pinfunction "8_8") (pintype "passive"))
    )
    (net (code "92") (name "/Реле4_13+") (class "Default")
      (node (ref "K50_4") (pin "8") (pinfunction "8_8") (pintype "passive"))
      (node (ref "K59_4") (pin "8") (pinfunction "8_8") (pintype "passive"))
    )
    (net (code "93") (name "/Реле4_14+") (class "Default")
      (node (ref "K44_4") (pin "8") (pinfunction "8_8") (pintype "passive"))
      (node (ref "K54_4") (pin "8") (pinfunction "8_8") (pintype "passive"))
    )
    (net (code "94") (name "/Реле4_15+") (class "Default")
      (node (ref "K51_4") (pin "8") (pinfunction "8_8") (pintype "passive"))
      (node (ref "K60_4") (pin "8") (pinfunction "8_8") (pintype "passive"))
    )
    (net (code "95") (name "/Реле4_16+") (class "Default")
      (node (ref "K45_4") (pin "8") (pinfunction "8_8") (pintype "passive"))
      (node (ref "K55_4") (pin "8") (pinfunction "8_8") (pintype "passive"))
    )
    (net (code "96") (name "/Реле4_17+") (class "Default")
      (node (ref "K46_4") (pin "8") (pinfunction "8_8") (pintype "passive"))
      (node (ref "K56_4") (pin "8") (pinfunction "8_8") (pintype "passive"))
    )
    (net (code "97") (name "/Реле4_18+") (class "Default")
      (node (ref "K47_4") (pin "8") (pinfunction "8_8") (pintype "passive"))
      (node (ref "K57_4") (pin "8") (pinfunction "8_8") (pintype "passive"))
    )
    (net (code "98") (name "unconnected-(K23_4-Pad2)") (class "Default")
      (node (ref "K23_4") (pin "2") (pinfunction "2_2") (pintype "passive"))
    )
    (net (code "99") (name "unconnected-(K23_4-Pad7)") (class "Default")
      (node (ref "K23_4") (pin "7") (pinfunction "7_7") (pintype "passive"))
    )
    (net (code "100") (name "unconnected-(K24_4-Pad2)") (class "Default")
      (node (ref "K24_4") (pin "2") (pinfunction "2_2") (pintype "passive"))
    )
    (net (code "101") (name "unconnected-(K24_4-Pad7)") (class "Default")
      (node (ref "K24_4") (pin "7") (pinfunction "7_7") (pintype "passive"))
    )
    (net (code "102") (name "unconnected-(K25_4-Pad2)") (class "Default")
      (node (ref "K25_4") (pin "2") (pinfunction "2_2") (pintype "passive"))
    )
    (net (code "103") (name "unconnected-(K25_4-Pad7)") (class "Default")
      (node (ref "K25_4") (pin "7") (pinfunction "7_7") (pintype "passive"))
    )
    (net (code "104") (name "unconnected-(K26_4-Pad2)") (class "Default")
      (node (ref "K26_4") (pin "2") (pinfunction "2_2") (pintype "passive"))
    )
    (net (code "105") (name "unconnected-(K26_4-Pad7)") (class "Default")
      (node (ref "K26_4") (pin "7") (pinfunction "7_7") (pintype "passive"))
    )
    (net (code "106") (name "unconnected-(K27_4-Pad2)") (class "Default")
      (node (ref "K27_4") (pin "2") (pinfunction "2_2") (pintype "passive"))
    )
    (net (code "107") (name "unconnected-(K27_4-Pad7)") (class "Default")
      (node (ref "K27_4") (pin "7") (pinfunction "7_7") (pintype "passive"))
    )
    (net (code "108") (name "unconnected-(K28_4-Pad2)") (class "Default")
      (node (ref "K28_4") (pin "2") (pinfunction "2_2") (pintype "passive"))
    )
    (net (code "109") (name "unconnected-(K28_4-Pad7)") (class "Default")
      (node (ref "K28_4") (pin "7") (pinfunction "7_7") (pintype "passive"))
    )
    (net (code "110") (name "unconnected-(K29_4-Pad2)") (class "Default")
      (node (ref "K29_4") (pin "2") (pinfunction "2_2") (pintype "passive"))
    )
    (net (code "111") (name "unconnected-(K29_4-Pad7)") (class "Default")
      (node (ref "K29_4") (pin "7") (pinfunction "7_7") (pintype "passive"))
    )
    (net (code "112") (name "unconnected-(K30_4-Pad2)") (class "Default")
      (node (ref "K30_4") (pin "2") (pinfunction "2_2") (pintype "passive"))
    )
    (net (code "113") (name "unconnected-(K30_4-Pad7)") (class "Default")
      (node (ref "K30_4") (pin "7") (pinfunction "7_7") (pintype "passive"))
    )
    (net (code "114") (name "unconnected-(K31_4-Pad2)") (class "Default")
      (node (ref "K31_4") (pin "2") (pinfunction "2_2") (pintype "passive"))
    )
    (net (code "115") (name "unconnected-(K31_4-Pad7)") (class "Default")
      (node (ref "K31_4") (pin "7") (pinfunction "7_7") (pintype "passive"))
    )
    (net (code "116") (name "unconnected-(K32_4-Pad2)") (class "Default")
      (node (ref "K32_4") (pin "2") (pinfunction "2_2") (pintype "passive"))
    )
    (net (code "117") (name "unconnected-(K32_4-Pad7)") (class "Default")
      (node (ref "K32_4") (pin "7") (pinfunction "7_7") (pintype "passive"))
    )
    (net (code "118") (name "unconnected-(K33_4-Pad2)") (class "Default")
      (node (ref "K33_4") (pin "2") (pinfunction "2_2") (pintype "passive"))
    )
    (net (code "119") (name "unconnected-(K33_4-Pad7)") (class "Default")
      (node (ref "K33_4") (pin "7") (pinfunction "7_7") (pintype "passive"))
    )
    (net (code "120") (name "unconnected-(K34_4-Pad2)") (class "Default")
      (node (ref "K34_4") (pin "2") (pinfunction "2_2") (pintype "passive"))
    )
    (net (code "121") (name "unconnected-(K34_4-Pad7)") (class "Default")
      (node (ref "K34_4") (pin "7") (pinfunction "7_7") (pintype "passive"))
    )
    (net (code "122") (name "unconnected-(K35_4-Pad2)") (class "Default")
      (node (ref "K35_4") (pin "2") (pinfunction "2_2") (pintype "passive"))
    )
    (net (code "123") (name "unconnected-(K35_4-Pad7)") (class "Default")
      (node (ref "K35_4") (pin "7") (pinfunction "7_7") (pintype "passive"))
    )
    (net (code "124") (name "unconnected-(K36_4-Pad2)") (class "Default")
      (node (ref "K36_4") (pin "2") (pinfunction "2_2") (pintype "passive"))
    )
    (net (code "125") (name "unconnected-(K36_4-Pad7)") (class "Default")
      (node (ref "K36_4") (pin "7") (pinfunction "7_7") (pintype "passive"))
    )
    (net (code "126") (name "unconnected-(K37_4-Pad2)") (class "Default")
      (node (ref "K37_4") (pin "2") (pinfunction "2_2") (pintype "passive"))
    )
    (net (code "127") (name "unconnected-(K37_4-Pad7)") (class "Default")
      (node (ref "K37_4") (pin "7") (pinfunction "7_7") (pintype "passive"))
    )
    (net (code "128") (name "unconnected-(K39_4-Pad2)") (class "Default")
      (node (ref "K39_4") (pin "2") (pinfunction "2_2") (pintype "passive"))
    )
    (net (code "129") (name "unconnected-(K39_4-Pad7)") (class "Default")
      (node (ref "K39_4") (pin "7") (pinfunction "7_7") (pintype "passive"))
    )
    (net (code "130") (name "unconnected-(K40_4-Pad2)") (class "Default")
      (node (ref "K40_4") (pin "2") (pinfunction "2_2") (pintype "passive"))
    )
    (net (code "131") (name "unconnected-(K40_4-Pad7)") (class "Default")
      (node (ref "K40_4") (pin "7") (pinfunction "7_7") (pintype "passive"))
    )
    (net (code "132") (name "unconnected-(K41_4-Pad2)") (class "Default")
      (node (ref "K41_4") (pin "2") (pinfunction "2_2") (pintype "passive"))
    )
    (net (code "133") (name "unconnected-(K41_4-Pad7)") (class "Default")
      (node (ref "K41_4") (pin "7") (pinfunction "7_7") (pintype "passive"))
    )
    (net (code "134") (name "unconnected-(K42_4-Pad2)") (class "Default")
      (node (ref "K42_4") (pin "2") (pinfunction "2_2") (pintype "passive"))
    )
    (net (code "135") (name "unconnected-(K42_4-Pad7)") (class "Default")
      (node (ref "K42_4") (pin "7") (pinfunction "7_7") (pintype "passive"))
    )
    (net (code "136") (name "unconnected-(K43_4-Pad2)") (class "Default")
      (node (ref "K43_4") (pin "2") (pinfunction "2_2") (pintype "passive"))
    )
    (net (code "137") (name "unconnected-(K43_4-Pad7)") (class "Default")
      (node (ref "K43_4") (pin "7") (pinfunction "7_7") (pintype "passive"))
    )
    (net (code "138") (name "unconnected-(K44_4-Pad2)") (class "Default")
      (node (ref "K44_4") (pin "2") (pinfunction "2_2") (pintype "passive"))
    )
    (net (code "139") (name "unconnected-(K44_4-Pad7)") (class "Default")
      (node (ref "K44_4") (pin "7") (pinfunction "7_7") (pintype "passive"))
    )
    (net (code "140") (name "unconnected-(K45_4-Pad2)") (class "Default")
      (node (ref "K45_4") (pin "2") (pinfunction "2_2") (pintype "passive"))
    )
    (net (code "141") (name "unconnected-(K45_4-Pad7)") (class "Default")
      (node (ref "K45_4") (pin "7") (pinfunction "7_7") (pintype "passive"))
    )
    (net (code "142") (name "unconnected-(K46_4-Pad2)") (class "Default")
      (node (ref "K46_4") (pin "2") (pinfunction "2_2") (pintype "passive"))
    )
    (net (code "143") (name "unconnected-(K46_4-Pad7)") (class "Default")
      (node (ref "K46_4") (pin "7") (pinfunction "7_7") (pintype "passive"))
    )
    (net (code "144") (name "unconnected-(K47_4-Pad2)") (class "Default")
      (node (ref "K47_4") (pin "2") (pinfunction "2_2") (pintype "passive"))
    )
    (net (code "145") (name "unconnected-(K47_4-Pad7)") (class "Default")
      (node (ref "K47_4") (pin "7") (pinfunction "7_7") (pintype "passive"))
    )
    (net (code "146") (name "unconnected-(K49_4-Pad2)") (class "Default")
      (node (ref "K49_4") (pin "2") (pinfunction "2_2") (pintype "passive"))
    )
    (net (code "147") (name "unconnected-(K49_4-Pad7)") (class "Default")
      (node (ref "K49_4") (pin "7") (pinfunction "7_7") (pintype "passive"))
    )
    (net (code "148") (name "unconnected-(K50_4-Pad2)") (class "Default")
      (node (ref "K50_4") (pin "2") (pinfunction "2_2") (pintype "passive"))
    )
    (net (code "149") (name "unconnected-(K50_4-Pad7)") (class "Default")
      (node (ref "K50_4") (pin "7") (pinfunction "7_7") (pintype "passive"))
    )
    (net (code "150") (name "unconnected-(K51_4-Pad2)") (class "Default")
      (node (ref "K51_4") (pin "2") (pinfunction "2_2") (pintype "passive"))
    )
    (net (code "151") (name "unconnected-(K51_4-Pad7)") (class "Default")
      (node (ref "K51_4") (pin "7") (pinfunction "7_7") (pintype "passive"))
    )
    (net (code "152") (name "unconnected-(K52_4-Pad2)") (class "Default")
      (node (ref "K52_4") (pin "2") (pinfunction "2_2") (pintype "passive"))
    )
    (net (code "153") (name "unconnected-(K52_4-Pad7)") (class "Default")
      (node (ref "K52_4") (pin "7") (pinfunction "7_7") (pintype "passive"))
    )
    (net (code "154") (name "unconnected-(K53_4-Pad2)") (class "Default")
      (node (ref "K53_4") (pin "2") (pinfunction "2_2") (pintype "passive"))
    )
    (net (code "155") (name "unconnected-(K53_4-Pad7)") (class "Default")
      (node (ref "K53_4") (pin "7") (pinfunction "7_7") (pintype "passive"))
    )
    (net (code "156") (name "unconnected-(K54_4-Pad2)") (class "Default")
      (node (ref "K54_4") (pin "2") (pinfunction "2_2") (pintype "passive"))
    )
    (net (code "157") (name "unconnected-(K54_4-Pad7)") (class "Default")
      (node (ref "K54_4") (pin "7") (pinfunction "7_7") (pintype "passive"))
    )
    (net (code "158") (name "unconnected-(K55_4-Pad2)") (class "Default")
      (node (ref "K55_4") (pin "2") (pinfunction "2_2") (pintype "passive"))
    )
    (net (code "159") (name "unconnected-(K55_4-Pad7)") (class "Default")
      (node (ref "K55_4") (pin "7") (pinfunction "7_7") (pintype "passive"))
    )
    (net (code "160") (name "unconnected-(K56_4-Pad2)") (class "Default")
      (node (ref "K56_4") (pin "2") (pinfunction "2_2") (pintype "passive"))
    )
    (net (code "161") (name "unconnected-(K56_4-Pad7)") (class "Default")
      (node (ref "K56_4") (pin "7") (pinfunction "7_7") (pintype "passive"))
    )
    (net (code "162") (name "unconnected-(K57_4-Pad2)") (class "Default")
      (node (ref "K57_4") (pin "2") (pinfunction "2_2") (pintype "passive"))
    )
    (net (code "163") (name "unconnected-(K57_4-Pad7)") (class "Default")
      (node (ref "K57_4") (pin "7") (pinfunction "7_7") (pintype "passive"))
    )
    (net (code "164") (name "unconnected-(K58_4-Pad2)") (class "Default")
      (node (ref "K58_4") (pin "2") (pinfunction "2_2") (pintype "passive"))
    )
    (net (code "165") (name "unconnected-(K58_4-Pad7)") (class "Default")
      (node (ref "K58_4") (pin "7") (pinfunction "7_7") (pintype "passive"))
    )
    (net (code "166") (name "unconnected-(K59_4-Pad2)") (class "Default")
      (node (ref "K59_4") (pin "2") (pinfunction "2_2") (pintype "passive"))
    )
    (net (code "167") (name "unconnected-(K59_4-Pad7)") (class "Default")
      (node (ref "K59_4") (pin "7") (pinfunction "7_7") (pintype "passive"))
    )
    (net (code "168") (name "unconnected-(K60_4-Pad2)") (class "Default")
      (node (ref "K60_4") (pin "2") (pinfunction "2_2") (pintype "passive"))
    )
    (net (code "169") (name "unconnected-(K60_4-Pad7)") (class "Default")
      (node (ref "K60_4") (pin "7") (pinfunction "7_7") (pintype "passive"))
    )
  )
)
